# Heaters.net
KiCad netlist of a schematic drawn in EAGLE
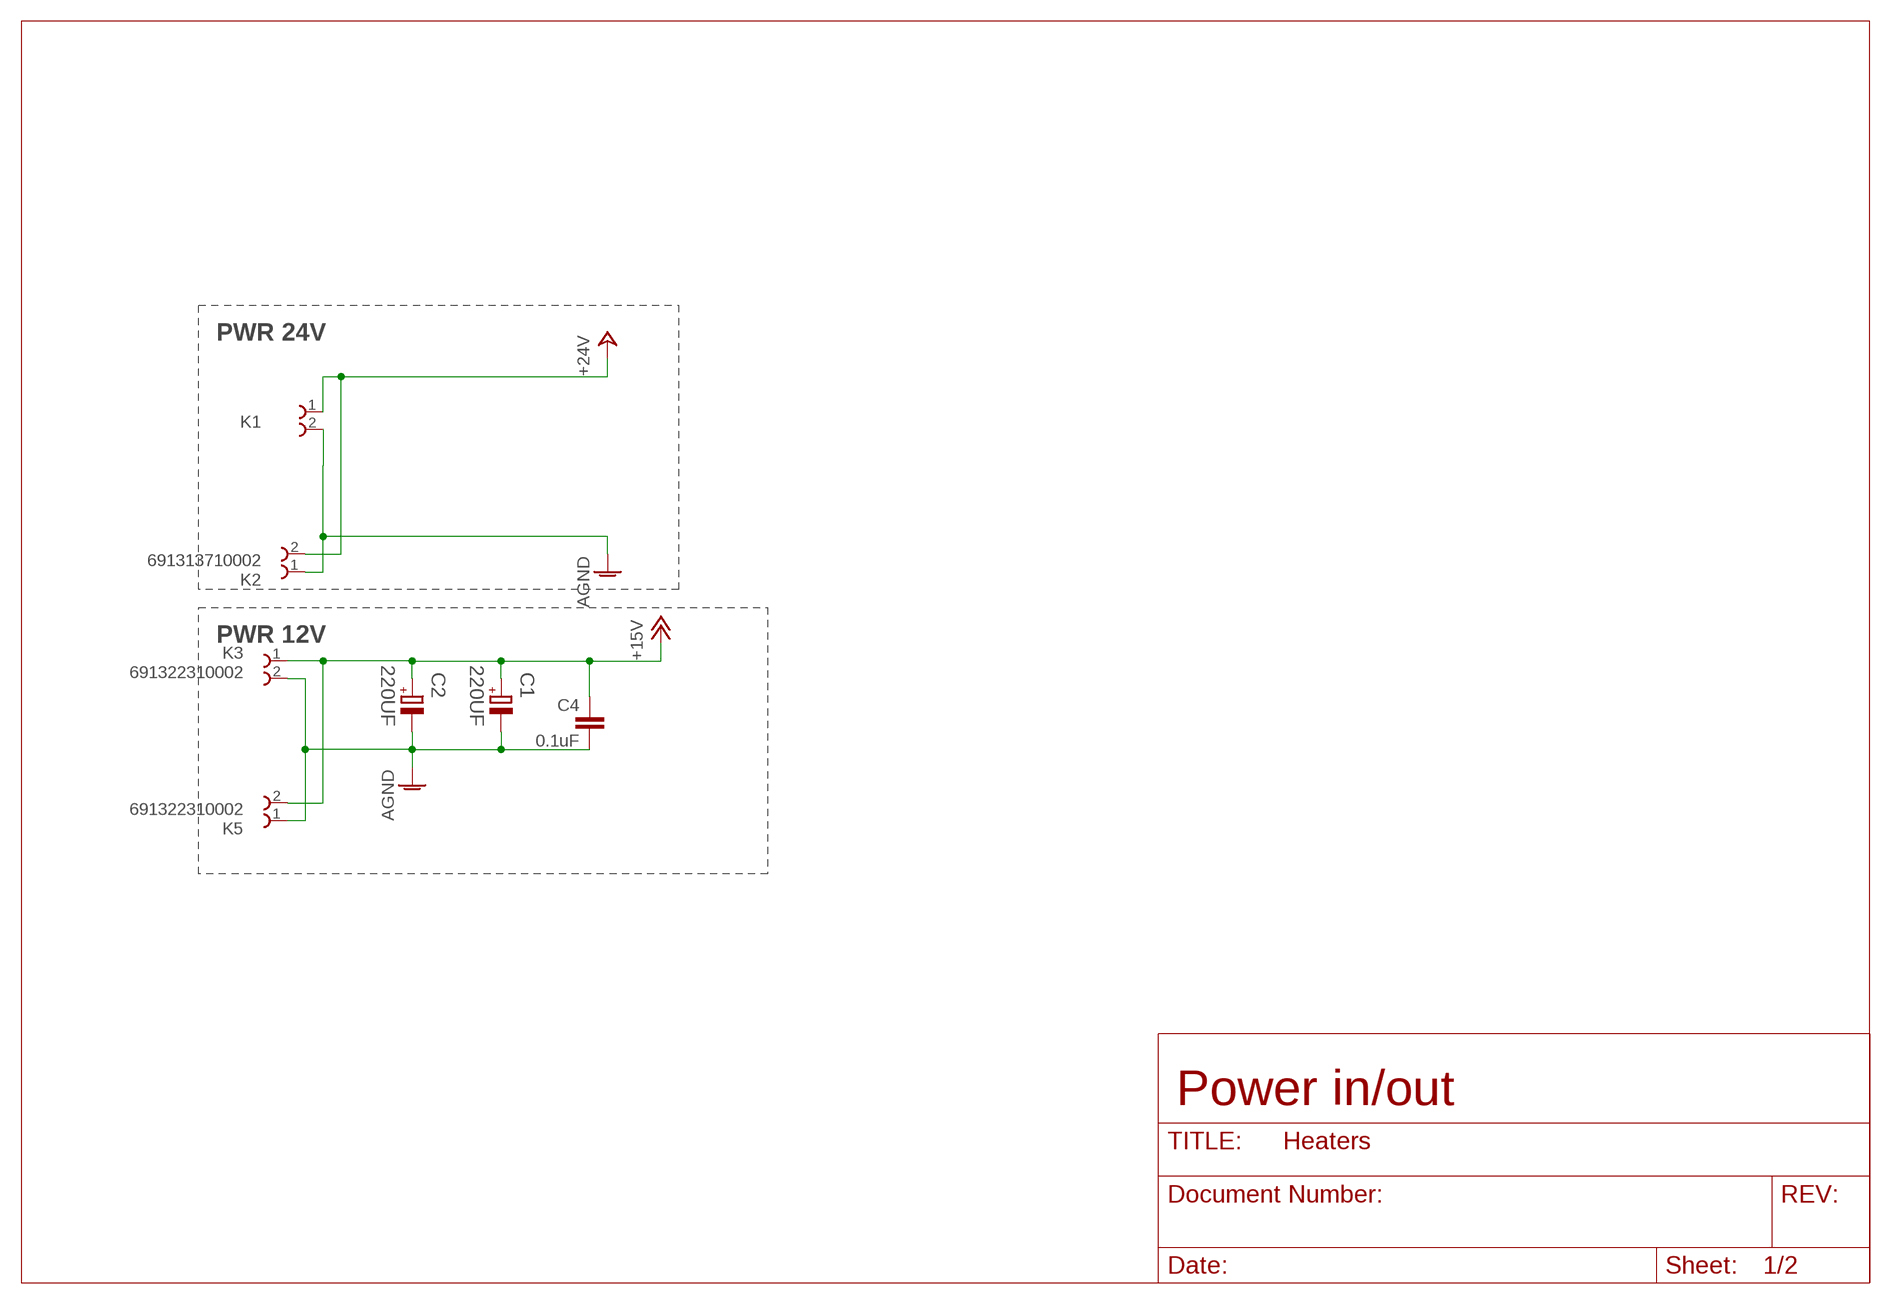
[diagram p0: schematic, sheet 1]
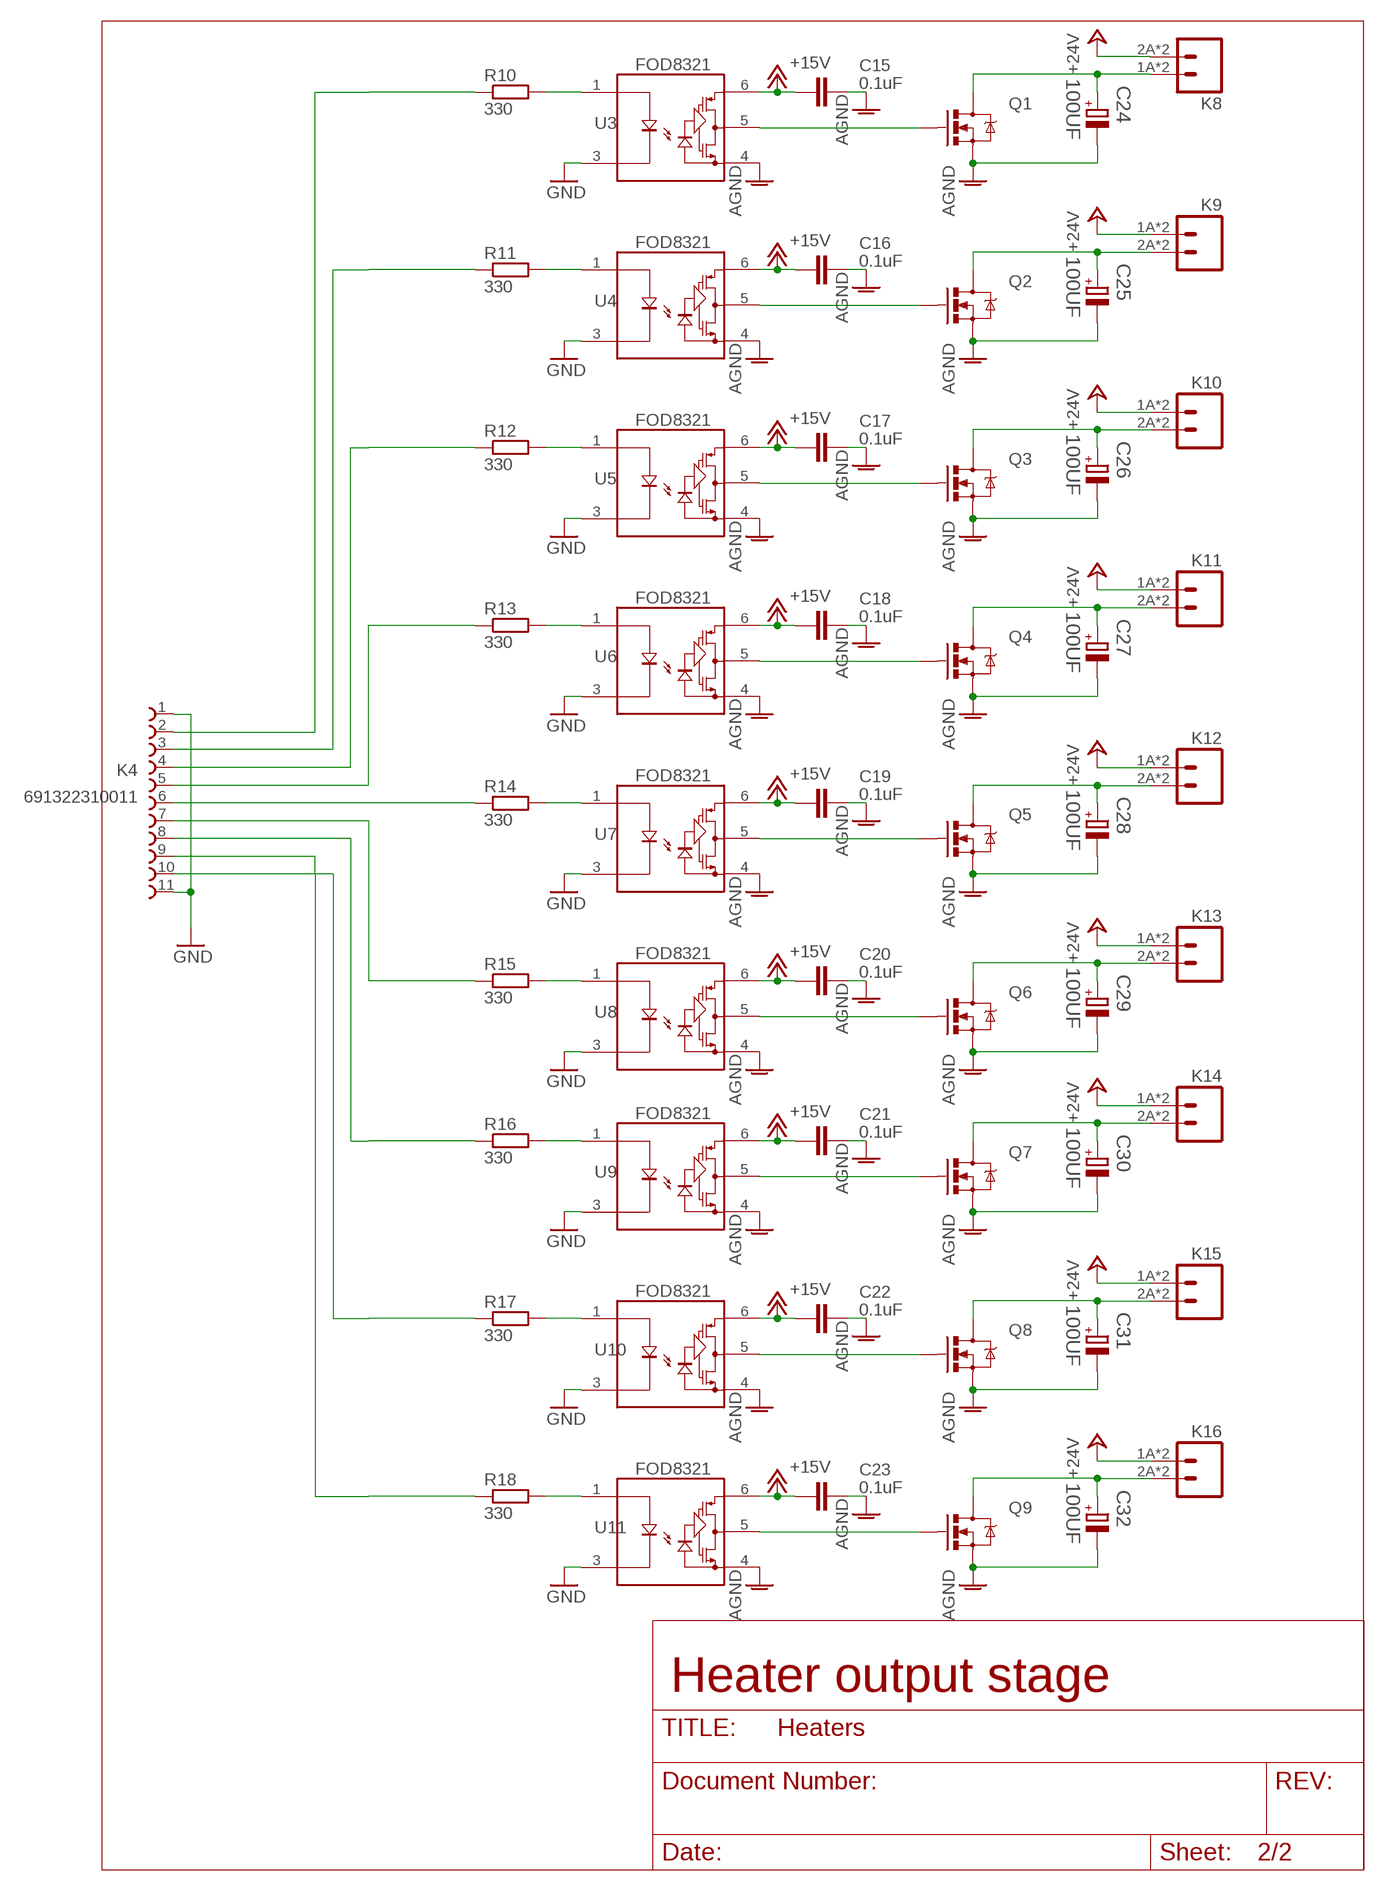
[diagram p1: schematic, sheet 2]

(export (version "E")
  (design (tool "Eeschema 10.0.6"))
  (components
    (comp (ref "C1")
      (value "220UF")
      (footprint "eagle-import:CAPAE830X1050N")
      (fields (field (name "MPN") "EEE-FP1V221AP") (field (name "TOLERANCE") "±20 %"))
      (libsource (lib "eagle-import") (part "EEE--CASE-FFP1V221AP"))
    )
    (comp (ref "C2")
      (value "220UF")
      (footprint "eagle-import:CAPAE830X1050N")
      (fields (field (name "MPN") "EEE-FP1V221AP") (field (name "TOLERANCE") "±20 %"))
      (libsource (lib "eagle-import") (part "EEE--CASE-FFP1V221AP"))
    )
    (comp (ref "C4")
      (value "0.1uF")
      (footprint "eagle-import:C0603K")
      (libsource (lib "eagle-import") (part "C-EUC0603K"))
    )
    (comp (ref "K1")
      (value "691313710002")
      (footprint "eagle-import:691313710002")
      (libsource (lib "eagle-import") (part "691313710002"))
    )
    (comp (ref "K2")
      (value "691313710002")
      (footprint "eagle-import:691313710002")
      (libsource (lib "eagle-import") (part "691313710002"))
    )
    (comp (ref "K3")
      (value "691322310002")
      (footprint "eagle-import:691322310002")
      (libsource (lib "eagle-import") (part "691322310002"))
    )
    (comp (ref "K5")
      (value "691322310002")
      (footprint "eagle-import:691322310002")
      (libsource (lib "eagle-import") (part "691322310002"))
    )
    (comp (ref "C15")
      (value "0.1uF")
      (footprint "eagle-import:C1206K")
      (libsource (lib "eagle-import") (part "C-EUC1206K"))
    )
    (comp (ref "C16")
      (value "0.1uF")
      (footprint "eagle-import:C1206K")
      (libsource (lib "eagle-import") (part "C-EUC1206K"))
    )
    (comp (ref "C17")
      (value "0.1uF")
      (footprint "eagle-import:C1206K")
      (libsource (lib "eagle-import") (part "C-EUC1206K"))
    )
    (comp (ref "C18")
      (value "0.1uF")
      (footprint "eagle-import:C1206K")
      (libsource (lib "eagle-import") (part "C-EUC1206K"))
    )
    (comp (ref "C19")
      (value "0.1uF")
      (footprint "eagle-import:C1206K")
      (libsource (lib "eagle-import") (part "C-EUC1206K"))
    )
    (comp (ref "C20")
      (value "0.1uF")
      (footprint "eagle-import:C1206K")
      (libsource (lib "eagle-import") (part "C-EUC1206K"))
    )
    (comp (ref "C21")
      (value "0.1uF")
      (footprint "eagle-import:C1206K")
      (libsource (lib "eagle-import") (part "C-EUC1206K"))
    )
    (comp (ref "C22")
      (value "0.1uF")
      (footprint "eagle-import:C1206K")
      (libsource (lib "eagle-import") (part "C-EUC1206K"))
    )
    (comp (ref "C23")
      (value "0.1uF")
      (footprint "eagle-import:C1206K")
      (libsource (lib "eagle-import") (part "C-EUC1206K"))
    )
    (comp (ref "C24")
      (value "100UF")
      (footprint "eagle-import:CAPAE1700X1700N")
      (fields (field (name "MPN") "EEE-FK2A101AM") (field (name "TOLERANCE") "±20 %"))
      (libsource (lib "eagle-import") (part "EEE--CASE-J16FK2A101AM"))
    )
    (comp (ref "C25")
      (value "100UF")
      (footprint "eagle-import:CAPAE1700X1700N")
      (fields (field (name "MPN") "EEE-FK2A101AM") (field (name "TOLERANCE") "±20 %"))
      (libsource (lib "eagle-import") (part "EEE--CASE-J16FK2A101AM"))
    )
    (comp (ref "C26")
      (value "100UF")
      (footprint "eagle-import:CAPAE1700X1700N")
      (fields (field (name "MPN") "EEE-FK2A101AM") (field (name "TOLERANCE") "±20 %"))
      (libsource (lib "eagle-import") (part "EEE--CASE-J16FK2A101AM"))
    )
    (comp (ref "C27")
      (value "100UF")
      (footprint "eagle-import:CAPAE1700X1700N")
      (fields (field (name "MPN") "EEE-FK2A101AM") (field (name "TOLERANCE") "±20 %"))
      (libsource (lib "eagle-import") (part "EEE--CASE-J16FK2A101AM"))
    )
    (comp (ref "C28")
      (value "100UF")
      (footprint "eagle-import:CAPAE1700X1700N")
      (fields (field (name "MPN") "EEE-FK2A101AM") (field (name "TOLERANCE") "±20 %"))
      (libsource (lib "eagle-import") (part "EEE--CASE-J16FK2A101AM"))
    )
    (comp (ref "C29")
      (value "100UF")
      (footprint "eagle-import:CAPAE1700X1700N")
      (fields (field (name "MPN") "EEE-FK2A101AM") (field (name "TOLERANCE") "±20 %"))
      (libsource (lib "eagle-import") (part "EEE--CASE-J16FK2A101AM"))
    )
    (comp (ref "C30")
      (value "100UF")
      (footprint "eagle-import:CAPAE1700X1700N")
      (fields (field (name "MPN") "EEE-FK2A101AM") (field (name "TOLERANCE") "±20 %"))
      (libsource (lib "eagle-import") (part "EEE--CASE-J16FK2A101AM"))
    )
    (comp (ref "C31")
      (value "100UF")
      (footprint "eagle-import:CAPAE1700X1700N")
      (fields (field (name "MPN") "EEE-FK2A101AM") (field (name "TOLERANCE") "±20 %"))
      (libsource (lib "eagle-import") (part "EEE--CASE-J16FK2A101AM"))
    )
    (comp (ref "C32")
      (value "100UF")
      (footprint "eagle-import:CAPAE1700X1700N")
      (fields (field (name "MPN") "EEE-FK2A101AM") (field (name "TOLERANCE") "±20 %"))
      (libsource (lib "eagle-import") (part "EEE--CASE-J16FK2A101AM"))
    )
    (comp (ref "K4")
      (value "691322310011")
      (footprint "eagle-import:691322310011")
      (libsource (lib "eagle-import") (part "691322310011"))
    )
    (comp (ref "K8")
      (value "M02-MOLEX-104188-0210")
      (footprint "eagle-import:LITE-TRAP-CONNECTOR-2")
      (libsource (lib "eagle-import") (part "M02-MOLEX-104188-0210"))
    )
    (comp (ref "K9")
      (value "M02-MOLEX-104188-0210")
      (footprint "eagle-import:LITE-TRAP-CONNECTOR-2")
      (libsource (lib "eagle-import") (part "M02-MOLEX-104188-0210"))
    )
    (comp (ref "K10")
      (value "M02-MOLEX-104188-0210")
      (footprint "eagle-import:LITE-TRAP-CONNECTOR-2")
      (libsource (lib "eagle-import") (part "M02-MOLEX-104188-0210"))
    )
    (comp (ref "K11")
      (value "M02-MOLEX-104188-0210")
      (footprint "eagle-import:LITE-TRAP-CONNECTOR-2")
      (libsource (lib "eagle-import") (part "M02-MOLEX-104188-0210"))
    )
    (comp (ref "K12")
      (value "M02-MOLEX-104188-0210")
      (footprint "eagle-import:LITE-TRAP-CONNECTOR-2")
      (libsource (lib "eagle-import") (part "M02-MOLEX-104188-0210"))
    )
    (comp (ref "K13")
      (value "M02-MOLEX-104188-0210")
      (footprint "eagle-import:LITE-TRAP-CONNECTOR-2")
      (libsource (lib "eagle-import") (part "M02-MOLEX-104188-0210"))
    )
    (comp (ref "K14")
      (value "M02-MOLEX-104188-0210")
      (footprint "eagle-import:LITE-TRAP-CONNECTOR-2")
      (libsource (lib "eagle-import") (part "M02-MOLEX-104188-0210"))
    )
    (comp (ref "K15")
      (value "M02-MOLEX-104188-0210")
      (footprint "eagle-import:LITE-TRAP-CONNECTOR-2")
      (libsource (lib "eagle-import") (part "M02-MOLEX-104188-0210"))
    )
    (comp (ref "K16")
      (value "M02-MOLEX-104188-0210")
      (footprint "eagle-import:LITE-TRAP-CONNECTOR-2")
      (libsource (lib "eagle-import") (part "M02-MOLEX-104188-0210"))
    )
    (comp (ref "Q1")
      (value "MOSFET-NCHANNEL-FDMS5672")
      (footprint "eagle-import:POWERPACK5060-8")
      (libsource (lib "eagle-import") (part "MOSFET-NCHANNEL-FDMS5672"))
    )
    (comp (ref "Q2")
      (value "MOSFET-NCHANNEL-FDMS5672")
      (footprint "eagle-import:POWERPACK5060-8")
      (libsource (lib "eagle-import") (part "MOSFET-NCHANNEL-FDMS5672"))
    )
    (comp (ref "Q3")
      (value "MOSFET-NCHANNEL-FDMS5672")
      (footprint "eagle-import:POWERPACK5060-8")
      (libsource (lib "eagle-import") (part "MOSFET-NCHANNEL-FDMS5672"))
    )
    (comp (ref "Q4")
      (value "MOSFET-NCHANNEL-FDMS5672")
      (footprint "eagle-import:POWERPACK5060-8")
      (libsource (lib "eagle-import") (part "MOSFET-NCHANNEL-FDMS5672"))
    )
    (comp (ref "Q5")
      (value "MOSFET-NCHANNEL-FDMS5672")
      (footprint "eagle-import:POWERPACK5060-8")
      (libsource (lib "eagle-import") (part "MOSFET-NCHANNEL-FDMS5672"))
    )
    (comp (ref "Q6")
      (value "MOSFET-NCHANNEL-FDMS5672")
      (footprint "eagle-import:POWERPACK5060-8")
      (libsource (lib "eagle-import") (part "MOSFET-NCHANNEL-FDMS5672"))
    )
    (comp (ref "Q7")
      (value "MOSFET-NCHANNEL-FDMS5672")
      (footprint "eagle-import:POWERPACK5060-8")
      (libsource (lib "eagle-import") (part "MOSFET-NCHANNEL-FDMS5672"))
    )
    (comp (ref "Q8")
      (value "MOSFET-NCHANNEL-FDMS5672")
      (footprint "eagle-import:POWERPACK5060-8")
      (libsource (lib "eagle-import") (part "MOSFET-NCHANNEL-FDMS5672"))
    )
    (comp (ref "Q9")
      (value "MOSFET-NCHANNEL-FDMS5672")
      (footprint "eagle-import:POWERPACK5060-8")
      (libsource (lib "eagle-import") (part "MOSFET-NCHANNEL-FDMS5672"))
    )
    (comp (ref "R10")
      (value "330")
      (footprint "eagle-import:R0603")
      (libsource (lib "eagle-import") (part "R-EU_R0603"))
    )
    (comp (ref "R11")
      (value "330")
      (footprint "eagle-import:R0603")
      (libsource (lib "eagle-import") (part "R-EU_R0603"))
    )
    (comp (ref "R12")
      (value "330")
      (footprint "eagle-import:R0603")
      (libsource (lib "eagle-import") (part "R-EU_R0603"))
    )
    (comp (ref "R13")
      (value "330")
      (footprint "eagle-import:R0603")
      (libsource (lib "eagle-import") (part "R-EU_R0603"))
    )
    (comp (ref "R14")
      (value "330")
      (footprint "eagle-import:R0603")
      (libsource (lib "eagle-import") (part "R-EU_R0603"))
    )
    (comp (ref "R15")
      (value "330")
      (footprint "eagle-import:R0603")
      (libsource (lib "eagle-import") (part "R-EU_R0603"))
    )
    (comp (ref "R16")
      (value "330")
      (footprint "eagle-import:R0603")
      (libsource (lib "eagle-import") (part "R-EU_R0603"))
    )
    (comp (ref "R17")
      (value "330")
      (footprint "eagle-import:R0603")
      (libsource (lib "eagle-import") (part "R-EU_R0603"))
    )
    (comp (ref "R18")
      (value "330")
      (footprint "eagle-import:R0603")
      (libsource (lib "eagle-import") (part "R-EU_R0603"))
    )
    (comp (ref "U3")
      (value "FOD8321")
      (footprint "eagle-import:WB-SOP5")
      (libsource (lib "eagle-import") (part "FOD8321"))
    )
    (comp (ref "U4")
      (value "FOD8321")
      (footprint "eagle-import:WB-SOP5")
      (libsource (lib "eagle-import") (part "FOD8321"))
    )
    (comp (ref "U5")
      (value "FOD8321")
      (footprint "eagle-import:WB-SOP5")
      (libsource (lib "eagle-import") (part "FOD8321"))
    )
    (comp (ref "U6")
      (value "FOD8321")
      (footprint "eagle-import:WB-SOP5")
      (libsource (lib "eagle-import") (part "FOD8321"))
    )
    (comp (ref "U7")
      (value "FOD8321")
      (footprint "eagle-import:WB-SOP5")
      (libsource (lib "eagle-import") (part "FOD8321"))
    )
    (comp (ref "U8")
      (value "FOD8321")
      (footprint "eagle-import:WB-SOP5")
      (libsource (lib "eagle-import") (part "FOD8321"))
    )
    (comp (ref "U9")
      (value "FOD8321")
      (footprint "eagle-import:WB-SOP5")
      (libsource (lib "eagle-import") (part "FOD8321"))
    )
    (comp (ref "U10")
      (value "FOD8321")
      (footprint "eagle-import:WB-SOP5")
      (libsource (lib "eagle-import") (part "FOD8321"))
    )
    (comp (ref "U11")
      (value "FOD8321")
      (footprint "eagle-import:WB-SOP5")
      (libsource (lib "eagle-import") (part "FOD8321"))
    )
  )
  (nets
    (net (code "1") (name "+15V") (class "Default")
      (node (ref "C1") (pin "1") (pinfunction "1_1") (pintype "passive"))
      (node (ref "C15") (pin "1") (pinfunction "1_1") (pintype "passive"))
      (node (ref "C16") (pin "1") (pinfunction "1_1") (pintype "passive"))
      (node (ref "C17") (pin "1") (pinfunction "1_1") (pintype "passive"))
      (node (ref "C18") (pin "1") (pinfunction "1_1") (pintype "passive"))
      (node (ref "C19") (pin "1") (pinfunction "1_1") (pintype "passive"))
      (node (ref "C2") (pin "1") (pinfunction "1_1") (pintype "passive"))
      (node (ref "C20") (pin "1") (pinfunction "1_1") (pintype "passive"))
      (node (ref "C21") (pin "1") (pinfunction "1_1") (pintype "passive"))
      (node (ref "C22") (pin "1") (pinfunction "1_1") (pintype "passive"))
      (node (ref "C23") (pin "1") (pinfunction "1_1") (pintype "passive"))
      (node (ref "C4") (pin "2") (pinfunction "2_2") (pintype "passive"))
      (node (ref "K3") (pin "1") (pinfunction "1_1") (pintype "passive"))
      (node (ref "K5") (pin "2") (pinfunction "2_2") (pintype "passive"))
      (node (ref "U10") (pin "6") (pinfunction "VDD_6") (pintype "bidirectional"))
      (node (ref "U11") (pin "6") (pinfunction "VDD_6") (pintype "bidirectional"))
      (node (ref "U3") (pin "6") (pinfunction "VDD_6") (pintype "bidirectional"))
      (node (ref "U4") (pin "6") (pinfunction "VDD_6") (pintype "bidirectional"))
      (node (ref "U5") (pin "6") (pinfunction "VDD_6") (pintype "bidirectional"))
      (node (ref "U6") (pin "6") (pinfunction "VDD_6") (pintype "bidirectional"))
      (node (ref "U7") (pin "6") (pinfunction "VDD_6") (pintype "bidirectional"))
      (node (ref "U8") (pin "6") (pinfunction "VDD_6") (pintype "bidirectional"))
      (node (ref "U9") (pin "6") (pinfunction "VDD_6") (pintype "bidirectional"))
    )
    (net (code "2") (name "+24V") (class "Default")
      (node (ref "K1") (pin "1") (pinfunction "1_1") (pintype "passive"))
      (node (ref "K10") (pin "1A") (pinfunction "1_1A") (pintype "passive"))
      (node (ref "K10") (pin "1B") (pinfunction "1_1B") (pintype "passive"))
      (node (ref "K11") (pin "1A") (pinfunction "1_1A") (pintype "passive"))
      (node (ref "K11") (pin "1B") (pinfunction "1_1B") (pintype "passive"))
      (node (ref "K12") (pin "1A") (pinfunction "1_1A") (pintype "passive"))
      (node (ref "K12") (pin "1B") (pinfunction "1_1B") (pintype "passive"))
      (node (ref "K13") (pin "1A") (pinfunction "1_1A") (pintype "passive"))
      (node (ref "K13") (pin "1B") (pinfunction "1_1B") (pintype "passive"))
      (node (ref "K14") (pin "1A") (pinfunction "1_1A") (pintype "passive"))
      (node (ref "K14") (pin "1B") (pinfunction "1_1B") (pintype "passive"))
      (node (ref "K15") (pin "1A") (pinfunction "1_1A") (pintype "passive"))
      (node (ref "K15") (pin "1B") (pinfunction "1_1B") (pintype "passive"))
      (node (ref "K16") (pin "1A") (pinfunction "1_1A") (pintype "passive"))
      (node (ref "K16") (pin "1B") (pinfunction "1_1B") (pintype "passive"))
      (node (ref "K2") (pin "2") (pinfunction "2_2") (pintype "passive"))
      (node (ref "K8") (pin "2A") (pinfunction "2_2A") (pintype "passive"))
      (node (ref "K8") (pin "2B") (pinfunction "2_2B") (pintype "passive"))
      (node (ref "K9") (pin "1A") (pinfunction "1_1A") (pintype "passive"))
      (node (ref "K9") (pin "1B") (pinfunction "1_1B") (pintype "passive"))
    )
    (net (code "3") (name "AGND") (class "Default")
      (node (ref "C1") (pin "2") (pinfunction "2_2") (pintype "passive"))
      (node (ref "C15") (pin "2") (pinfunction "2_2") (pintype "passive"))
      (node (ref "C16") (pin "2") (pinfunction "2_2") (pintype "passive"))
      (node (ref "C17") (pin "2") (pinfunction "2_2") (pintype "passive"))
      (node (ref "C18") (pin "2") (pinfunction "2_2") (pintype "passive"))
      (node (ref "C19") (pin "2") (pinfunction "2_2") (pintype "passive"))
      (node (ref "C2") (pin "2") (pinfunction "2_2") (pintype "passive"))
      (node (ref "C20") (pin "2") (pinfunction "2_2") (pintype "passive"))
      (node (ref "C21") (pin "2") (pinfunction "2_2") (pintype "passive"))
      (node (ref "C22") (pin "2") (pinfunction "2_2") (pintype "passive"))
      (node (ref "C23") (pin "2") (pinfunction "2_2") (pintype "passive"))
      (node (ref "C24") (pin "2") (pinfunction "2_2") (pintype "passive"))
      (node (ref "C25") (pin "2") (pinfunction "2_2") (pintype "passive"))
      (node (ref "C26") (pin "2") (pinfunction "2_2") (pintype "passive"))
      (node (ref "C27") (pin "2") (pinfunction "2_2") (pintype "passive"))
      (node (ref "C28") (pin "2") (pinfunction "2_2") (pintype "passive"))
      (node (ref "C29") (pin "2") (pinfunction "2_2") (pintype "passive"))
      (node (ref "C30") (pin "2") (pinfunction "2_2") (pintype "passive"))
      (node (ref "C31") (pin "2") (pinfunction "2_2") (pintype "passive"))
      (node (ref "C32") (pin "2") (pinfunction "2_2") (pintype "passive"))
      (node (ref "C4") (pin "1") (pinfunction "1_1") (pintype "passive"))
      (node (ref "K1") (pin "2") (pinfunction "2_2") (pintype "passive"))
      (node (ref "K2") (pin "1") (pinfunction "1_1") (pintype "passive"))
      (node (ref "K3") (pin "2") (pinfunction "2_2") (pintype "passive"))
      (node (ref "K5") (pin "1") (pinfunction "1_1") (pintype "passive"))
      (node (ref "Q1") (pin "S1") (pinfunction "S_S1") (pintype "passive"))
      (node (ref "Q1") (pin "S2") (pinfunction "S_S2") (pintype "passive"))
      (node (ref "Q1") (pin "S3") (pinfunction "S_S3") (pintype "passive"))
      (node (ref "Q2") (pin "S1") (pinfunction "S_S1") (pintype "passive"))
      (node (ref "Q2") (pin "S2") (pinfunction "S_S2") (pintype "passive"))
      (node (ref "Q2") (pin "S3") (pinfunction "S_S3") (pintype "passive"))
      (node (ref "Q3") (pin "S1") (pinfunction "S_S1") (pintype "passive"))
      (node (ref "Q3") (pin "S2") (pinfunction "S_S2") (pintype "passive"))
      (node (ref "Q3") (pin "S3") (pinfunction "S_S3") (pintype "passive"))
      (node (ref "Q4") (pin "S1") (pinfunction "S_S1") (pintype "passive"))
      (node (ref "Q4") (pin "S2") (pinfunction "S_S2") (pintype "passive"))
      (node (ref "Q4") (pin "S3") (pinfunction "S_S3") (pintype "passive"))
      (node (ref "Q5") (pin "S1") (pinfunction "S_S1") (pintype "passive"))
      (node (ref "Q5") (pin "S2") (pinfunction "S_S2") (pintype "passive"))
      (node (ref "Q5") (pin "S3") (pinfunction "S_S3") (pintype "passive"))
      (node (ref "Q6") (pin "S1") (pinfunction "S_S1") (pintype "passive"))
      (node (ref "Q6") (pin "S2") (pinfunction "S_S2") (pintype "passive"))
      (node (ref "Q6") (pin "S3") (pinfunction "S_S3") (pintype "passive"))
      (node (ref "Q7") (pin "S1") (pinfunction "S_S1") (pintype "passive"))
      (node (ref "Q7") (pin "S2") (pinfunction "S_S2") (pintype "passive"))
      (node (ref "Q7") (pin "S3") (pinfunction "S_S3") (pintype "passive"))
      (node (ref "Q8") (pin "S1") (pinfunction "S_S1") (pintype "passive"))
      (node (ref "Q8") (pin "S2") (pinfunction "S_S2") (pintype "passive"))
      (node (ref "Q8") (pin "S3") (pinfunction "S_S3") (pintype "passive"))
      (node (ref "Q9") (pin "S1") (pinfunction "S_S1") (pintype "passive"))
      (node (ref "Q9") (pin "S2") (pinfunction "S_S2") (pintype "passive"))
      (node (ref "Q9") (pin "S3") (pinfunction "S_S3") (pintype "passive"))
      (node (ref "U10") (pin "4") (pinfunction "VSS_4") (pintype "bidirectional"))
      (node (ref "U11") (pin "4") (pinfunction "VSS_4") (pintype "bidirectional"))
      (node (ref "U3") (pin "4") (pinfunction "VSS_4") (pintype "bidirectional"))
      (node (ref "U4") (pin "4") (pinfunction "VSS_4") (pintype "bidirectional"))
      (node (ref "U5") (pin "4") (pinfunction "VSS_4") (pintype "bidirectional"))
      (node (ref "U6") (pin "4") (pinfunction "VSS_4") (pintype "bidirectional"))
      (node (ref "U7") (pin "4") (pinfunction "VSS_4") (pintype "bidirectional"))
      (node (ref "U8") (pin "4") (pinfunction "VSS_4") (pintype "bidirectional"))
      (node (ref "U9") (pin "4") (pinfunction "VSS_4") (pintype "bidirectional"))
    )
    (net (code "4") (name "GND") (class "Default")
      (node (ref "K4") (pin "1") (pinfunction "1_1") (pintype "passive"))
      (node (ref "K4") (pin "11") (pinfunction "11_11") (pintype "passive"))
      (node (ref "U10") (pin "3") (pinfunction "K_3") (pintype "bidirectional"))
      (node (ref "U11") (pin "3") (pinfunction "K_3") (pintype "bidirectional"))
      (node (ref "U3") (pin "3") (pinfunction "K_3") (pintype "bidirectional"))
      (node (ref "U4") (pin "3") (pinfunction "K_3") (pintype "bidirectional"))
      (node (ref "U5") (pin "3") (pinfunction "K_3") (pintype "bidirectional"))
      (node (ref "U6") (pin "3") (pinfunction "K_3") (pintype "bidirectional"))
      (node (ref "U7") (pin "3") (pinfunction "K_3") (pintype "bidirectional"))
      (node (ref "U8") (pin "3") (pinfunction "K_3") (pintype "bidirectional"))
      (node (ref "U9") (pin "3") (pinfunction "K_3") (pintype "bidirectional"))
    )
    (net (code "5") (name "Net-(C24-Pad1)") (class "Default")
      (node (ref "C24") (pin "1") (pinfunction "1_1") (pintype "passive"))
      (node (ref "K8") (pin "1A") (pinfunction "1_1A") (pintype "passive"))
      (node (ref "K8") (pin "1B") (pinfunction "1_1B") (pintype "passive"))
      (node (ref "Q1") (pin "D5") (pinfunction "D_D5") (pintype "passive"))
      (node (ref "Q1") (pin "D6") (pinfunction "D_D6") (pintype "passive"))
      (node (ref "Q1") (pin "D7") (pinfunction "D_D7") (pintype "passive"))
      (node (ref "Q1") (pin "D8") (pinfunction "D_D8") (pintype "passive"))
      (node (ref "Q1") (pin "DPAD") (pinfunction "D_DPAD") (pintype "passive"))
    )
    (net (code "6") (name "Net-(C25-Pad1)") (class "Default")
      (node (ref "C25") (pin "1") (pinfunction "1_1") (pintype "passive"))
      (node (ref "K9") (pin "2A") (pinfunction "2_2A") (pintype "passive"))
      (node (ref "K9") (pin "2B") (pinfunction "2_2B") (pintype "passive"))
      (node (ref "Q2") (pin "D5") (pinfunction "D_D5") (pintype "passive"))
      (node (ref "Q2") (pin "D6") (pinfunction "D_D6") (pintype "passive"))
      (node (ref "Q2") (pin "D7") (pinfunction "D_D7") (pintype "passive"))
      (node (ref "Q2") (pin "D8") (pinfunction "D_D8") (pintype "passive"))
      (node (ref "Q2") (pin "DPAD") (pinfunction "D_DPAD") (pintype "passive"))
    )
    (net (code "7") (name "Net-(C26-Pad1)") (class "Default")
      (node (ref "C26") (pin "1") (pinfunction "1_1") (pintype "passive"))
      (node (ref "K10") (pin "2A") (pinfunction "2_2A") (pintype "passive"))
      (node (ref "K10") (pin "2B") (pinfunction "2_2B") (pintype "passive"))
      (node (ref "Q3") (pin "D5") (pinfunction "D_D5") (pintype "passive"))
      (node (ref "Q3") (pin "D6") (pinfunction "D_D6") (pintype "passive"))
      (node (ref "Q3") (pin "D7") (pinfunction "D_D7") (pintype "passive"))
      (node (ref "Q3") (pin "D8") (pinfunction "D_D8") (pintype "passive"))
      (node (ref "Q3") (pin "DPAD") (pinfunction "D_DPAD") (pintype "passive"))
    )
    (net (code "8") (name "Net-(C27-Pad1)") (class "Default")
      (node (ref "C27") (pin "1") (pinfunction "1_1") (pintype "passive"))
      (node (ref "K11") (pin "2A") (pinfunction "2_2A") (pintype "passive"))
      (node (ref "K11") (pin "2B") (pinfunction "2_2B") (pintype "passive"))
      (node (ref "Q4") (pin "D5") (pinfunction "D_D5") (pintype "passive"))
      (node (ref "Q4") (pin "D6") (pinfunction "D_D6") (pintype "passive"))
      (node (ref "Q4") (pin "D7") (pinfunction "D_D7") (pintype "passive"))
      (node (ref "Q4") (pin "D8") (pinfunction "D_D8") (pintype "passive"))
      (node (ref "Q4") (pin "DPAD") (pinfunction "D_DPAD") (pintype "passive"))
    )
    (net (code "9") (name "Net-(C28-Pad1)") (class "Default")
      (node (ref "C28") (pin "1") (pinfunction "1_1") (pintype "passive"))
      (node (ref "K12") (pin "2A") (pinfunction "2_2A") (pintype "passive"))
      (node (ref "K12") (pin "2B") (pinfunction "2_2B") (pintype "passive"))
      (node (ref "Q5") (pin "D5") (pinfunction "D_D5") (pintype "passive"))
      (node (ref "Q5") (pin "D6") (pinfunction "D_D6") (pintype "passive"))
      (node (ref "Q5") (pin "D7") (pinfunction "D_D7") (pintype "passive"))
      (node (ref "Q5") (pin "D8") (pinfunction "D_D8") (pintype "passive"))
      (node (ref "Q5") (pin "DPAD") (pinfunction "D_DPAD") (pintype "passive"))
    )
    (net (code "10") (name "Net-(C29-Pad1)") (class "Default")
      (node (ref "C29") (pin "1") (pinfunction "1_1") (pintype "passive"))
      (node (ref "K13") (pin "2A") (pinfunction "2_2A") (pintype "passive"))
      (node (ref "K13") (pin "2B") (pinfunction "2_2B") (pintype "passive"))
      (node (ref "Q6") (pin "D5") (pinfunction "D_D5") (pintype "passive"))
      (node (ref "Q6") (pin "D6") (pinfunction "D_D6") (pintype "passive"))
      (node (ref "Q6") (pin "D7") (pinfunction "D_D7") (pintype "passive"))
      (node (ref "Q6") (pin "D8") (pinfunction "D_D8") (pintype "passive"))
      (node (ref "Q6") (pin "DPAD") (pinfunction "D_DPAD") (pintype "passive"))
    )
    (net (code "11") (name "Net-(C30-Pad1)") (class "Default")
      (node (ref "C30") (pin "1") (pinfunction "1_1") (pintype "passive"))
      (node (ref "K14") (pin "2A") (pinfunction "2_2A") (pintype "passive"))
      (node (ref "K14") (pin "2B") (pinfunction "2_2B") (pintype "passive"))
      (node (ref "Q7") (pin "D5") (pinfunction "D_D5") (pintype "passive"))
      (node (ref "Q7") (pin "D6") (pinfunction "D_D6") (pintype "passive"))
      (node (ref "Q7") (pin "D7") (pinfunction "D_D7") (pintype "passive"))
      (node (ref "Q7") (pin "D8") (pinfunction "D_D8") (pintype "passive"))
      (node (ref "Q7") (pin "DPAD") (pinfunction "D_DPAD") (pintype "passive"))
    )
    (net (code "12") (name "Net-(C31-Pad1)") (class "Default")
      (node (ref "C31") (pin "1") (pinfunction "1_1") (pintype "passive"))
      (node (ref "K15") (pin "2A") (pinfunction "2_2A") (pintype "passive"))
      (node (ref "K15") (pin "2B") (pinfunction "2_2B") (pintype "passive"))
      (node (ref "Q8") (pin "D5") (pinfunction "D_D5") (pintype "passive"))
      (node (ref "Q8") (pin "D6") (pinfunction "D_D6") (pintype "passive"))
      (node (ref "Q8") (pin "D7") (pinfunction "D_D7") (pintype "passive"))
      (node (ref "Q8") (pin "D8") (pinfunction "D_D8") (pintype "passive"))
      (node (ref "Q8") (pin "DPAD") (pinfunction "D_DPAD") (pintype "passive"))
    )
    (net (code "13") (name "Net-(C32-Pad1)") (class "Default")
      (node (ref "C32") (pin "1") (pinfunction "1_1") (pintype "passive"))
      (node (ref "K16") (pin "2A") (pinfunction "2_2A") (pintype "passive"))
      (node (ref "K16") (pin "2B") (pinfunction "2_2B") (pintype "passive"))
      (node (ref "Q9") (pin "D5") (pinfunction "D_D5") (pintype "passive"))
      (node (ref "Q9") (pin "D6") (pinfunction "D_D6") (pintype "passive"))
      (node (ref "Q9") (pin "D7") (pinfunction "D_D7") (pintype "passive"))
      (node (ref "Q9") (pin "D8") (pinfunction "D_D8") (pintype "passive"))
      (node (ref "Q9") (pin "DPAD") (pinfunction "D_DPAD") (pintype "passive"))
    )
    (net (code "14") (name "Net-(K4-Pad2)") (class "Default")
      (node (ref "K4") (pin "2") (pinfunction "2_2") (pintype "passive"))
      (node (ref "R10") (pin "1") (pinfunction "1_1") (pintype "passive"))
    )
    (net (code "15") (name "Net-(K4-Pad3)") (class "Default")
      (node (ref "K4") (pin "3") (pinfunction "3_3") (pintype "passive"))
      (node (ref "R11") (pin "1") (pinfunction "1_1") (pintype "passive"))
    )
    (net (code "16") (name "Net-(K4-Pad4)") (class "Default")
      (node (ref "K4") (pin "4") (pinfunction "4_4") (pintype "passive"))
      (node (ref "R12") (pin "1") (pinfunction "1_1") (pintype "passive"))
    )
    (net (code "17") (name "Net-(K4-Pad5)") (class "Default")
      (node (ref "K4") (pin "5") (pinfunction "5_5") (pintype "passive"))
      (node (ref "R13") (pin "1") (pinfunction "1_1") (pintype "passive"))
    )
    (net (code "18") (name "Net-(K4-Pad6)") (class "Default")
      (node (ref "K4") (pin "6") (pinfunction "6_6") (pintype "passive"))
      (node (ref "R14") (pin "1") (pinfunction "1_1") (pintype "passive"))
    )
    (net (code "19") (name "Net-(K4-Pad7)") (class "Default")
      (node (ref "K4") (pin "7") (pinfunction "7_7") (pintype "passive"))
      (node (ref "R15") (pin "1") (pinfunction "1_1") (pintype "passive"))
    )
    (net (code "20") (name "Net-(K4-Pad8)") (class "Default")
      (node (ref "K4") (pin "8") (pinfunction "8_8") (pintype "passive"))
      (node (ref "R16") (pin "1") (pinfunction "1_1") (pintype "passive"))
    )
    (net (code "21") (name "Net-(K4-Pad9)") (class "Default")
      (node (ref "K4") (pin "9") (pinfunction "9_9") (pintype "passive"))
      (node (ref "R18") (pin "1") (pinfunction "1_1") (pintype "passive"))
    )
    (net (code "22") (name "Net-(K4-Pad10)") (class "Default")
      (node (ref "K4") (pin "10") (pinfunction "10_10") (pintype "passive"))
      (node (ref "R17") (pin "1") (pinfunction "1_1") (pintype "passive"))
    )
    (net (code "23") (name "Net-(Q1-G)") (class "Default")
      (node (ref "Q1") (pin "G4") (pinfunction "G_G4") (pintype "passive"))
      (node (ref "U3") (pin "5") (pinfunction "VO_5") (pintype "bidirectional"))
    )
    (net (code "24") (name "Net-(Q2-G)") (class "Default")
      (node (ref "Q2") (pin "G4") (pinfunction "G_G4") (pintype "passive"))
      (node (ref "U4") (pin "5") (pinfunction "VO_5") (pintype "bidirectional"))
    )
    (net (code "25") (name "Net-(Q3-G)") (class "Default")
      (node (ref "Q3") (pin "G4") (pinfunction "G_G4") (pintype "passive"))
      (node (ref "U5") (pin "5") (pinfunction "VO_5") (pintype "bidirectional"))
    )
    (net (code "26") (name "Net-(Q4-G)") (class "Default")
      (node (ref "Q4") (pin "G4") (pinfunction "G_G4") (pintype "passive"))
      (node (ref "U6") (pin "5") (pinfunction "VO_5") (pintype "bidirectional"))
    )
    (net (code "27") (name "Net-(Q5-G)") (class "Default")
      (node (ref "Q5") (pin "G4") (pinfunction "G_G4") (pintype "passive"))
      (node (ref "U7") (pin "5") (pinfunction "VO_5") (pintype "bidirectional"))
    )
    (net (code "28") (name "Net-(Q6-G)") (class "Default")
      (node (ref "Q6") (pin "G4") (pinfunction "G_G4") (pintype "passive"))
      (node (ref "U8") (pin "5") (pinfunction "VO_5") (pintype "bidirectional"))
    )
    (net (code "29") (name "Net-(Q7-G)") (class "Default")
      (node (ref "Q7") (pin "G4") (pinfunction "G_G4") (pintype "passive"))
      (node (ref "U9") (pin "5") (pinfunction "VO_5") (pintype "bidirectional"))
    )
    (net (code "30") (name "Net-(Q8-G)") (class "Default")
      (node (ref "Q8") (pin "G4") (pinfunction "G_G4") (pintype "passive"))
      (node (ref "U10") (pin "5") (pinfunction "VO_5") (pintype "bidirectional"))
    )
    (net (code "31") (name "Net-(Q9-G)") (class "Default")
      (node (ref "Q9") (pin "G4") (pinfunction "G_G4") (pintype "passive"))
      (node (ref "U11") (pin "5") (pinfunction "VO_5") (pintype "bidirectional"))
    )
    (net (code "32") (name "Net-(U3-A)") (class "Default")
      (node (ref "R10") (pin "2") (pinfunction "2_2") (pintype "passive"))
      (node (ref "U3") (pin "1") (pinfunction "A_1") (pintype "bidirectional"))
    )
    (net (code "33") (name "Net-(U4-A)") (class "Default")
      (node (ref "R11") (pin "2") (pinfunction "2_2") (pintype "passive"))
      (node (ref "U4") (pin "1") (pinfunction "A_1") (pintype "bidirectional"))
    )
    (net (code "34") (name "Net-(U5-A)") (class "Default")
      (node (ref "R12") (pin "2") (pinfunction "2_2") (pintype "passive"))
      (node (ref "U5") (pin "1") (pinfunction "A_1") (pintype "bidirectional"))
    )
    (net (code "35") (name "Net-(U6-A)") (class "Default")
      (node (ref "R13") (pin "2") (pinfunction "2_2") (pintype "passive"))
      (node (ref "U6") (pin "1") (pinfunction "A_1") (pintype "bidirectional"))
    )
    (net (code "36") (name "Net-(U7-A)") (class "Default")
      (node (ref "R14") (pin "2") (pinfunction "2_2") (pintype "passive"))
      (node (ref "U7") (pin "1") (pinfunction "A_1") (pintype "bidirectional"))
    )
    (net (code "37") (name "Net-(U8-A)") (class "Default")
      (node (ref "R15") (pin "2") (pinfunction "2_2") (pintype "passive"))
      (node (ref "U8") (pin "1") (pinfunction "A_1") (pintype "bidirectional"))
    )
    (net (code "38") (name "Net-(U9-A)") (class "Default")
      (node (ref "R16") (pin "2") (pinfunction "2_2") (pintype "passive"))
      (node (ref "U9") (pin "1") (pinfunction "A_1") (pintype "bidirectional"))
    )
    (net (code "39") (name "Net-(U10-A)") (class "Default")
      (node (ref "R17") (pin "2") (pinfunction "2_2") (pintype "passive"))
      (node (ref "U10") (pin "1") (pinfunction "A_1") (pintype "bidirectional"))
    )
    (net (code "40") (name "Net-(U11-A)") (class "Default")
      (node (ref "R18") (pin "2") (pinfunction "2_2") (pintype "passive"))
      (node (ref "U11") (pin "1") (pinfunction "A_1") (pintype "bidirectional"))
    )
  )
)
